# solenoid.net
KiCad netlist of a schematic drawn in EAGLE
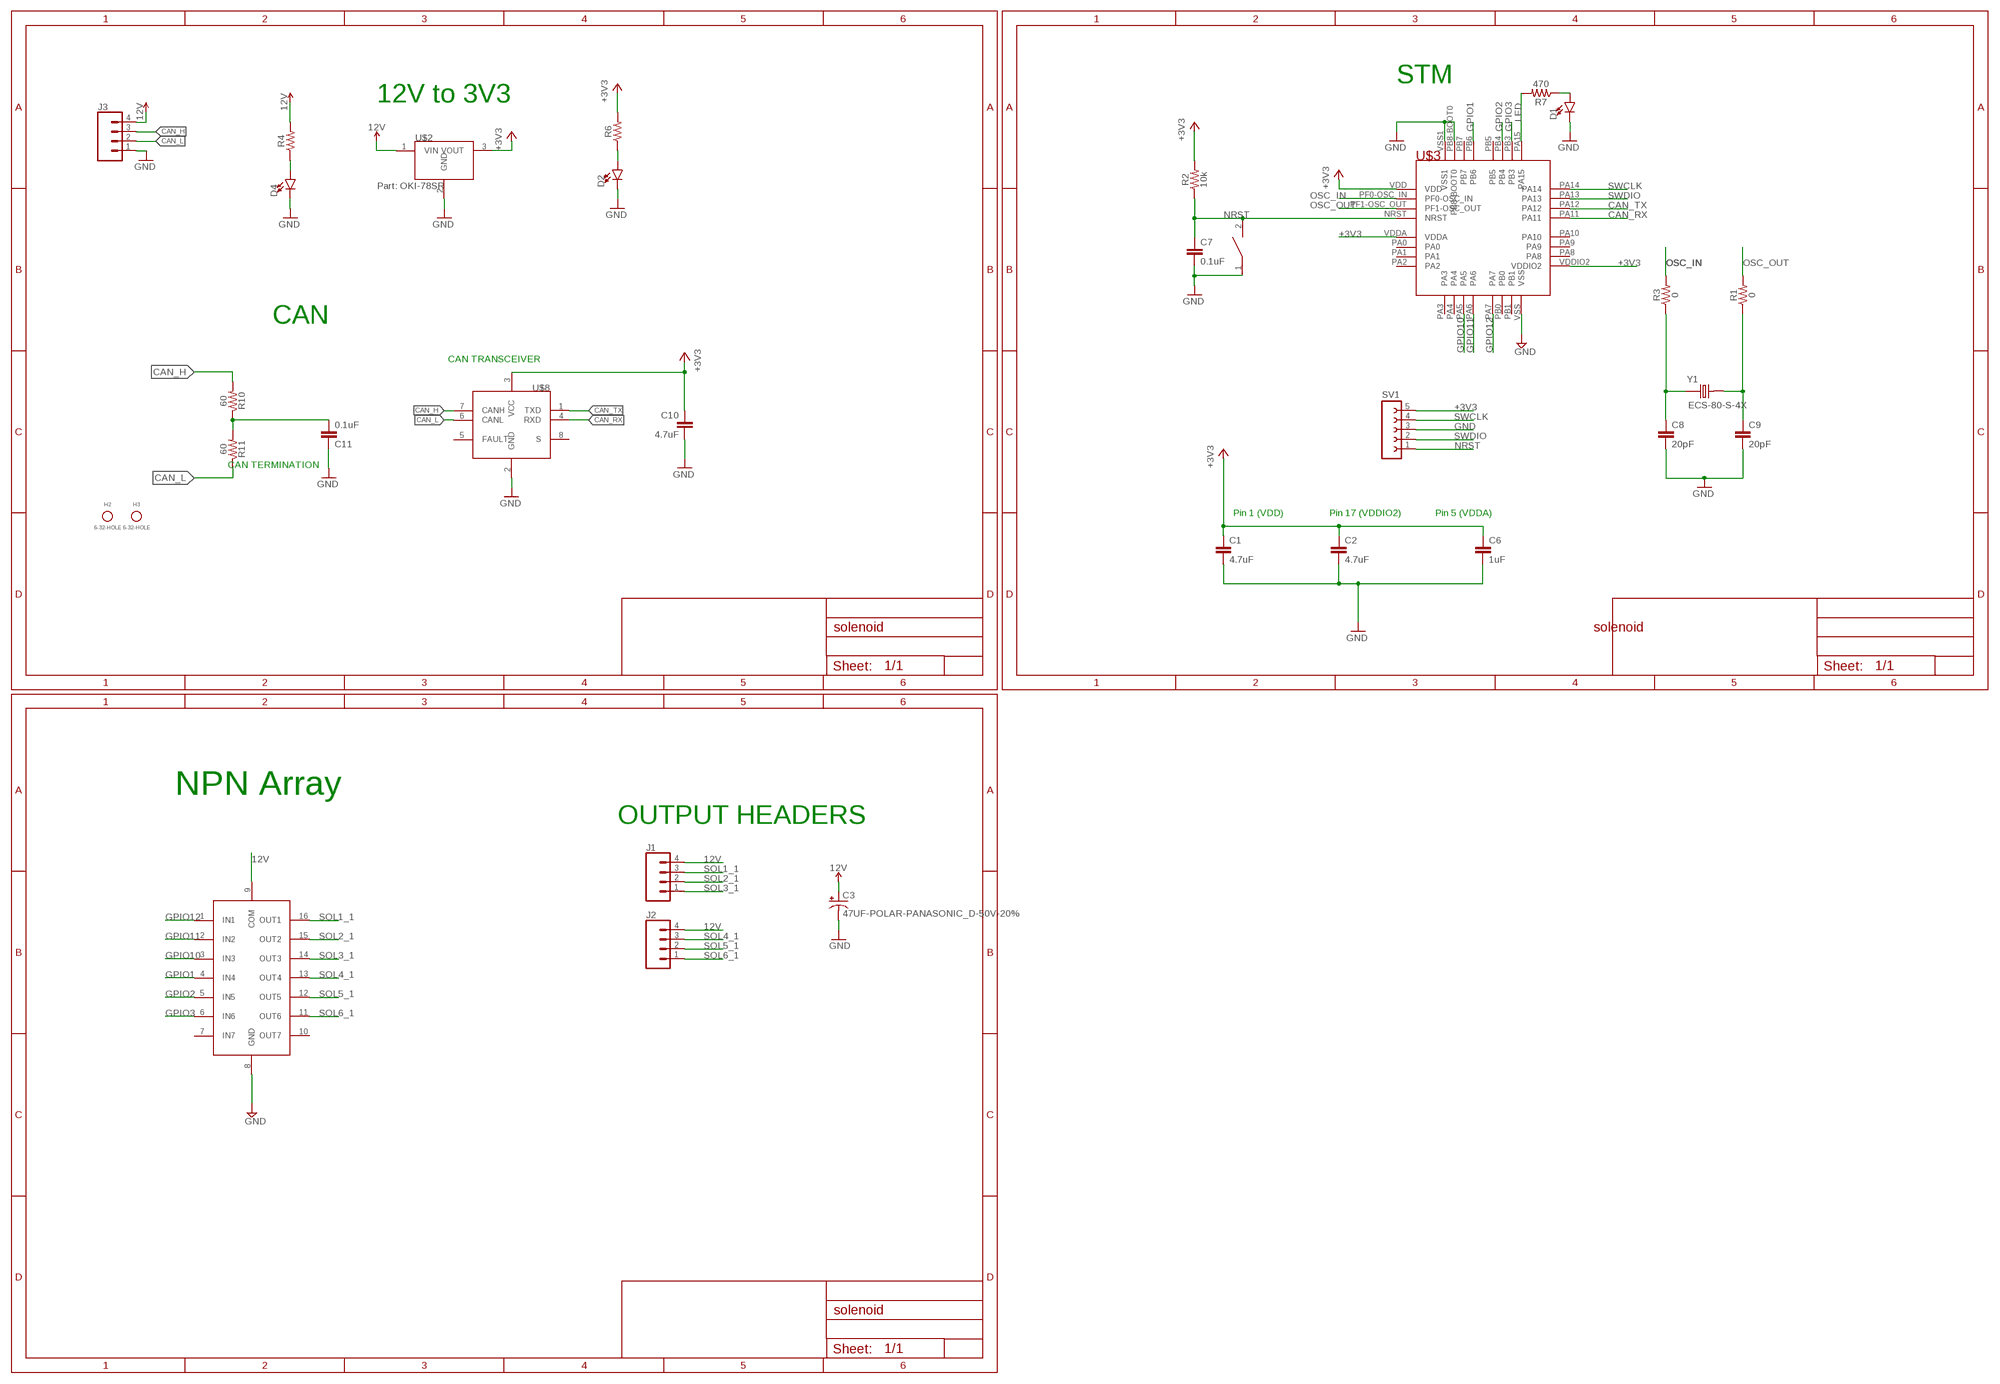
[diagram p0: schematic, sheet 1]

(export (version "E")
  (design (tool "Eeschema 10.0.6"))
  (components
    (comp (ref "C1")
      (value "4.7uF")
      (footprint "eagle-import:0603")
      (libsource (lib "eagle-import") (part "4.7UF0603"))
    )
    (comp (ref "C2")
      (value "4.7uF")
      (footprint "eagle-import:0603")
      (libsource (lib "eagle-import") (part "4.7UF0603"))
    )
    (comp (ref "C3")
      (value "47UF-POLAR-PANASONIC_D-50V-20%")
      (footprint "eagle-import:PANASONIC_D")
      (libsource (lib "eagle-import") (part "47UF-POLAR-PANASONIC_D-50V-20%"))
    )
    (comp (ref "C6")
      (value "1uF")
      (footprint "eagle-import:0603")
      (libsource (lib "eagle-import") (part "4.7UF0603"))
    )
    (comp (ref "C7")
      (value "0.1uF")
      (footprint "eagle-import:0603")
      (libsource (lib "eagle-import") (part "4.7UF0603"))
    )
    (comp (ref "C8")
      (value "20pF")
      (footprint "eagle-import:0603")
      (libsource (lib "eagle-import") (part "4.7UF0603"))
    )
    (comp (ref "C9")
      (value "20pF")
      (footprint "eagle-import:0603")
      (libsource (lib "eagle-import") (part "4.7UF0603"))
    )
    (comp (ref "C10")
      (value "4.7uF")
      (footprint "eagle-import:0603")
      (libsource (lib "eagle-import") (part "4.7UF0603"))
    )
    (comp (ref "C11")
      (value "0.1uF")
      (footprint "eagle-import:0603")
      (libsource (lib "eagle-import") (part "0.1UF-0603-25V-(+80/-20%)"))
    )
    (comp (ref "D1")
      (value "LED0603")
      (footprint "eagle-import:LED-0603")
      (libsource (lib "eagle-import") (part "LED0603"))
    )
    (comp (ref "D2")
      (value "LED0603")
      (footprint "eagle-import:LED-0603")
      (libsource (lib "eagle-import") (part "LED0603"))
    )
    (comp (ref "D4")
      (value "LED0603")
      (footprint "eagle-import:LED-0603")
      (libsource (lib "eagle-import") (part "LED0603"))
    )
    (comp (ref "H2")
      (value "6-32-HOLE")
      (footprint "eagle-import:6-32-HOLE")
      (libsource (lib "eagle-import") (part "6-32-HOLE"))
    )
    (comp (ref "H3")
      (value "6-32-HOLE")
      (footprint "eagle-import:6-32-HOLE")
      (libsource (lib "eagle-import") (part "6-32-HOLE"))
    )
    (comp (ref "J1")
      (value "PXC-PTSM-04-V-1778573")
      (footprint "eagle-import:PXC-PTSM-04-V-1778573")
      (libsource (lib "eagle-import") (part "PXC-PTSM-04-V-1778573"))
    )
    (comp (ref "J2")
      (value "PXC-PTSM-04-V-1778573")
      (footprint "eagle-import:PXC-PTSM-04-V-1778573")
      (libsource (lib "eagle-import") (part "PXC-PTSM-04-V-1778573"))
    )
    (comp (ref "J3")
      (value "PXC-PTSM-04-V-1778573")
      (footprint "eagle-import:PXC-PTSM-04-V-1778573")
      (libsource (lib "eagle-import") (part "PXC-PTSM-04-V-1778573"))
    )
    (comp (ref "R1")
      (value "0")
      (footprint "eagle-import:0603")
      (libsource (lib "eagle-import") (part "1KOHM-0603-1/10W-1%"))
    )
    (comp (ref "R2")
      (value "10k")
      (footprint "eagle-import:0603")
      (libsource (lib "eagle-import") (part "1KOHM-0603-1/10W-1%"))
    )
    (comp (ref "R3")
      (value "0")
      (footprint "eagle-import:0603")
      (libsource (lib "eagle-import") (part "1KOHM-0603-1/10W-1%"))
    )
    (comp (ref "R4")
      (value "RESISTOR0603")
      (footprint "eagle-import:0603")
      (libsource (lib "eagle-import") (part "RESISTOR0603"))
    )
    (comp (ref "R6")
      (value "RESISTOR0603")
      (footprint "eagle-import:0603")
      (libsource (lib "eagle-import") (part "RESISTOR0603"))
    )
    (comp (ref "R7")
      (value "470")
      (footprint "eagle-import:0603")
      (libsource (lib "eagle-import") (part "RESISTOR0603"))
    )
    (comp (ref "R10")
      (value "60")
      (footprint "eagle-import:0603")
      (libsource (lib "eagle-import") (part "1KOHM-0603-1/10W-1%"))
    )
    (comp (ref "R11")
      (value "60")
      (footprint "eagle-import:0603")
      (libsource (lib "eagle-import") (part "1KOHM-0603-1/10W-1%"))
    )
    (comp (ref "SV1")
      (value "FE05-1")
      (footprint "eagle-import:FE05-1")
      (libsource (lib "eagle-import") (part "FE05-1"))
    )
    (comp (ref "U$1")
      (value "DISCRETECOMPONENTS_SWITCH")
      (footprint "eagle-import:DISCRETECOMPONENTS_SW_2512")
      (libsource (lib "eagle-import") (part "DISCRETECOMPONENTS_SWITCH"))
    )
    (comp (ref "U$2")
      (value "MURATA-DC-DC")
      (footprint "eagle-import:MURATA-DC-DC")
      (libsource (lib "eagle-import") (part "MURATA-DC-DC"))
    )
    (comp (ref "U$3")
      (value "STM32F042K6T6")
      (footprint "eagle-import:STM32F042K6T6")
      (libsource (lib "eagle-import") (part "STM32F042K6T6"))
    )
    (comp (ref "U$8")
      (value "TCAN337D")
      (footprint "eagle-import:SOIC-8")
      (libsource (lib "eagle-import") (part "TCAN337D"))
    )
    (comp (ref "U1")
      (value "ULN2003V12")
      (footprint "eagle-import:ULN2003V12")
      (fields (field (name "MANUFACTURER") "Diodes Inc."))
      (libsource (lib "eagle-import") (part "ULN2003V12"))
    )
    (comp (ref "Y1")
      (value "ECS-80-S-4X")
      (footprint "eagle-import:XTAL_ECS-80-S-4X")
      (fields (field (name "DIGI-KEY_PART_NUMBER") "X1057-ND") (field (name "MF") "ECS International"))
      (libsource (lib "eagle-import") (part "ECS-80-S-4X"))
    )
  )
  (nets
    (net (code "1") (name "+3V3") (class "Default")
      (node (ref "C1") (pin "1") (pinfunction "1_1") (pintype "passive"))
      (node (ref "C10") (pin "1") (pinfunction "1_1") (pintype "passive"))
      (node (ref "C2") (pin "1") (pinfunction "1_1") (pintype "passive"))
      (node (ref "C6") (pin "1") (pinfunction "1_1") (pintype "passive"))
      (node (ref "R2") (pin "2") (pinfunction "2_2") (pintype "passive"))
      (node (ref "R6") (pin "2") (pinfunction "2_2") (pintype "passive"))
      (node (ref "SV1") (pin "5") (pinfunction "5_5") (pintype "passive"))
      (node (ref "U$2") (pin "3") (pinfunction "VOUT_3") (pintype "bidirectional"))
      (node (ref "U$3") (pin "VDD") (pinfunction "VDD_VDD") (pintype "bidirectional"))
      (node (ref "U$3") (pin "VDDA") (pinfunction "VDDA_VDDA") (pintype "bidirectional"))
      (node (ref "U$3") (pin "VDDIO2") (pinfunction "VDDIO2_VDDIO2") (pintype "bidirectional"))
      (node (ref "U$8") (pin "3") (pinfunction "VCC_3") (pintype "bidirectional"))
    )
    (net (code "2") (name "/GPIO1") (class "Default")
      (node (ref "U$3") (pin "PB6") (pinfunction "PB6_PB6") (pintype "bidirectional"))
      (node (ref "U1") (pin "4") (pinfunction "IN4_4") (pintype "bidirectional"))
    )
    (net (code "3") (name "/GPIO2") (class "Default")
      (node (ref "U$3") (pin "PB4") (pinfunction "PB4_PB4") (pintype "bidirectional"))
      (node (ref "U1") (pin "5") (pinfunction "IN5_5") (pintype "bidirectional"))
    )
    (net (code "4") (name "/GPIO3") (class "Default")
      (node (ref "U$3") (pin "PB3") (pinfunction "PB3_PB3") (pintype "bidirectional"))
      (node (ref "U1") (pin "6") (pinfunction "IN6_6") (pintype "bidirectional"))
    )
    (net (code "5") (name "/GPIO10") (class "Default")
      (node (ref "U$3") (pin "PA5") (pinfunction "PA5_PA5") (pintype "bidirectional"))
      (node (ref "U1") (pin "3") (pinfunction "IN3_3") (pintype "bidirectional"))
    )
    (net (code "6") (name "/GPIO11") (class "Default")
      (node (ref "U$3") (pin "PA6") (pinfunction "PA6_PA6") (pintype "bidirectional"))
      (node (ref "U1") (pin "2") (pinfunction "IN2_2") (pintype "bidirectional"))
    )
    (net (code "7") (name "/GPIO12") (class "Default")
      (node (ref "U$3") (pin "PA7") (pinfunction "PA7_PA7") (pintype "bidirectional"))
      (node (ref "U1") (pin "1") (pinfunction "IN1_1") (pintype "bidirectional"))
    )
    (net (code "8") (name "/LED") (class "Default")
      (node (ref "R7") (pin "2") (pinfunction "2_2") (pintype "passive"))
      (node (ref "U$3") (pin "PA15") (pinfunction "PA15_PA15") (pintype "bidirectional"))
    )
    (net (code "9") (name "/NRST") (class "Default")
      (node (ref "C7") (pin "1") (pinfunction "1_1") (pintype "passive"))
      (node (ref "R2") (pin "1") (pinfunction "1_1") (pintype "passive"))
      (node (ref "SV1") (pin "1") (pinfunction "1_1") (pintype "passive"))
      (node (ref "U$1") (pin "2") (pinfunction "P$2_2") (pintype "bidirectional"))
      (node (ref "U$3") (pin "NRST") (pinfunction "NRST_NRST") (pintype "bidirectional"))
    )
    (net (code "10") (name "/OSC_IN") (class "Default")
      (node (ref "R3") (pin "2") (pinfunction "2_2") (pintype "passive"))
      (node (ref "U$3") (pin "PF0-OSC_IN") (pinfunction "PF0-OSC_IN_PF0-OSC_IN") (pintype "bidirectional"))
    )
    (net (code "11") (name "/OSC_OUT") (class "Default")
      (node (ref "R1") (pin "2") (pinfunction "2_2") (pintype "passive"))
      (node (ref "U$3") (pin "PF1-OSC_OUT") (pinfunction "PF1-OSC_OUT_PF1-OSC_OUT") (pintype "bidirectional"))
    )
    (net (code "12") (name "/SOL1_1") (class "Default")
      (node (ref "J1") (pin "3") (pinfunction "3_3") (pintype "passive"))
      (node (ref "U1") (pin "16") (pinfunction "OUT1_16") (pintype "bidirectional"))
    )
    (net (code "13") (name "/SOL2_1") (class "Default")
      (node (ref "J1") (pin "2") (pinfunction "2_2") (pintype "passive"))
      (node (ref "U1") (pin "15") (pinfunction "OUT2_15") (pintype "bidirectional"))
    )
    (net (code "14") (name "/SOL3_1") (class "Default")
      (node (ref "J1") (pin "1") (pinfunction "1_1") (pintype "passive"))
      (node (ref "U1") (pin "14") (pinfunction "OUT3_14") (pintype "bidirectional"))
    )
    (net (code "15") (name "/SOL4_1") (class "Default")
      (node (ref "J2") (pin "3") (pinfunction "3_3") (pintype "passive"))
      (node (ref "U1") (pin "13") (pinfunction "OUT4_13") (pintype "bidirectional"))
    )
    (net (code "16") (name "/SOL5_1") (class "Default")
      (node (ref "J2") (pin "2") (pinfunction "2_2") (pintype "passive"))
      (node (ref "U1") (pin "12") (pinfunction "OUT5_12") (pintype "bidirectional"))
    )
    (net (code "17") (name "/SOL6_1") (class "Default")
      (node (ref "J2") (pin "1") (pinfunction "1_1") (pintype "passive"))
      (node (ref "U1") (pin "11") (pinfunction "OUT6_11") (pintype "bidirectional"))
    )
    (net (code "18") (name "/SWCLK") (class "Default")
      (node (ref "SV1") (pin "4") (pinfunction "4_4") (pintype "passive"))
      (node (ref "U$3") (pin "PA14") (pinfunction "PA14_PA14") (pintype "bidirectional"))
    )
    (net (code "19") (name "/SWDIO") (class "Default")
      (node (ref "SV1") (pin "2") (pinfunction "2_2") (pintype "passive"))
      (node (ref "U$3") (pin "PA13") (pinfunction "PA13_PA13") (pintype "bidirectional"))
    )
    (net (code "20") (name "12V") (class "Default")
      (node (ref "C3") (pin "+") (pinfunction "+_+") (pintype "passive"))
      (node (ref "J1") (pin "4") (pinfunction "4_4") (pintype "passive"))
      (node (ref "J2") (pin "4") (pinfunction "4_4") (pintype "passive"))
      (node (ref "J3") (pin "4") (pinfunction "4_4") (pintype "passive"))
      (node (ref "R4") (pin "2") (pinfunction "2_2") (pintype "passive"))
      (node (ref "U$2") (pin "1") (pinfunction "VIN_1") (pintype "bidirectional"))
      (node (ref "U1") (pin "9") (pinfunction "COM_9") (pintype "bidirectional"))
    )
    (net (code "21") (name "CAN_H") (class "Default")
      (node (ref "J3") (pin "3") (pinfunction "3_3") (pintype "passive"))
      (node (ref "R10") (pin "2") (pinfunction "2_2") (pintype "passive"))
      (node (ref "U$8") (pin "7") (pinfunction "CANH_7") (pintype "bidirectional"))
    )
    (net (code "22") (name "CAN_L") (class "Default")
      (node (ref "J3") (pin "2") (pinfunction "2_2") (pintype "passive"))
      (node (ref "R11") (pin "1") (pinfunction "1_1") (pintype "passive"))
      (node (ref "U$8") (pin "6") (pinfunction "CANL_6") (pintype "bidirectional"))
    )
    (net (code "23") (name "CAN_RX") (class "Default")
      (node (ref "U$3") (pin "PA11") (pinfunction "PA11_PA11") (pintype "bidirectional"))
      (node (ref "U$8") (pin "4") (pinfunction "RXD_4") (pintype "bidirectional"))
    )
    (net (code "24") (name "CAN_TX") (class "Default")
      (node (ref "U$3") (pin "PA12") (pinfunction "PA12_PA12") (pintype "bidirectional"))
      (node (ref "U$8") (pin "1") (pinfunction "TXD_1") (pintype "bidirectional"))
    )
    (net (code "25") (name "GND") (class "Default")
      (node (ref "C1") (pin "2") (pinfunction "2_2") (pintype "passive"))
      (node (ref "C10") (pin "2") (pinfunction "2_2") (pintype "passive"))
      (node (ref "C11") (pin "1") (pinfunction "1_1") (pintype "passive"))
      (node (ref "C2") (pin "2") (pinfunction "2_2") (pintype "passive"))
      (node (ref "C3") (pin "-") (pinfunction "-_-") (pintype "passive"))
      (node (ref "C6") (pin "2") (pinfunction "2_2") (pintype "passive"))
      (node (ref "C7") (pin "2") (pinfunction "2_2") (pintype "passive"))
      (node (ref "C8") (pin "2") (pinfunction "2_2") (pintype "passive"))
      (node (ref "C9") (pin "2") (pinfunction "2_2") (pintype "passive"))
      (node (ref "D1") (pin "C") (pinfunction "C_C") (pintype "passive"))
      (node (ref "D2") (pin "C") (pinfunction "C_C") (pintype "passive"))
      (node (ref "D4") (pin "C") (pinfunction "C_C") (pintype "passive"))
      (node (ref "J3") (pin "1") (pinfunction "1_1") (pintype "passive"))
      (node (ref "SV1") (pin "3") (pinfunction "3_3") (pintype "passive"))
      (node (ref "U$1") (pin "1") (pinfunction "P$1_1") (pintype "bidirectional"))
      (node (ref "U$2") (pin "2") (pinfunction "GND_2") (pintype "bidirectional"))
      (node (ref "U$3") (pin "PB8-BOOT0") (pinfunction "PB8-BOOT0_PB8-BOOT0") (pintype "bidirectional"))
      (node (ref "U$3") (pin "VSS") (pinfunction "VSS_VSS") (pintype "bidirectional"))
      (node (ref "U$3") (pin "VSS1") (pinfunction "VSS1_VSS1") (pintype "bidirectional"))
      (node (ref "U$8") (pin "2") (pinfunction "GND_2") (pintype "bidirectional"))
      (node (ref "U1") (pin "8") (pinfunction "GND_8") (pintype "bidirectional"))
    )
    (net (code "26") (name "Net-(C8-Pad1)") (class "Default")
      (node (ref "C8") (pin "1") (pinfunction "1_1") (pintype "passive"))
      (node (ref "R3") (pin "1") (pinfunction "1_1") (pintype "passive"))
      (node (ref "Y1") (pin "1") (pinfunction "1_1") (pintype "passive"))
    )
    (net (code "27") (name "Net-(C9-Pad1)") (class "Default")
      (node (ref "C9") (pin "1") (pinfunction "1_1") (pintype "passive"))
      (node (ref "R1") (pin "1") (pinfunction "1_1") (pintype "passive"))
      (node (ref "Y1") (pin "2") (pinfunction "2_2") (pintype "passive"))
    )
    (net (code "28") (name "Net-(C11-Pad2)") (class "Default")
      (node (ref "C11") (pin "2") (pinfunction "2_2") (pintype "passive"))
      (node (ref "R10") (pin "1") (pinfunction "1_1") (pintype "passive"))
      (node (ref "R11") (pin "2") (pinfunction "2_2") (pintype "passive"))
    )
    (net (code "29") (name "Net-(D1-PadA)") (class "Default")
      (node (ref "D1") (pin "A") (pinfunction "A_A") (pintype "passive"))
      (node (ref "R7") (pin "1") (pinfunction "1_1") (pintype "passive"))
    )
    (net (code "30") (name "Net-(D2-PadA)") (class "Default")
      (node (ref "D2") (pin "A") (pinfunction "A_A") (pintype "passive"))
      (node (ref "R6") (pin "1") (pinfunction "1_1") (pintype "passive"))
    )
    (net (code "31") (name "Net-(D4-PadA)") (class "Default")
      (node (ref "D4") (pin "A") (pinfunction "A_A") (pintype "passive"))
      (node (ref "R4") (pin "1") (pinfunction "1_1") (pintype "passive"))
    )
    (net (code "32") (name "unconnected-(U$3-PadPA0)") (class "Default")
      (node (ref "U$3") (pin "PA0") (pinfunction "PA0_PA0") (pintype "bidirectional"))
    )
    (net (code "33") (name "unconnected-(U$3-PadPA1)") (class "Default")
      (node (ref "U$3") (pin "PA1") (pinfunction "PA1_PA1") (pintype "bidirectional"))
    )
    (net (code "34") (name "unconnected-(U$3-PadPA2)") (class "Default")
      (node (ref "U$3") (pin "PA2") (pinfunction "PA2_PA2") (pintype "bidirectional"))
    )
    (net (code "35") (name "unconnected-(U$3-PadPA3)") (class "Default")
      (node (ref "U$3") (pin "PA3") (pinfunction "PA3_PA3") (pintype "bidirectional"))
    )
    (net (code "36") (name "unconnected-(U$3-PadPA4)") (class "Default")
      (node (ref "U$3") (pin "PA4") (pinfunction "PA4_PA4") (pintype "bidirectional"))
    )
    (net (code "37") (name "unconnected-(U$3-PadPA8)") (class "Default")
      (node (ref "U$3") (pin "PA8") (pinfunction "PA8_PA8") (pintype "bidirectional"))
    )
    (net (code "38") (name "unconnected-(U$3-PadPA9)") (class "Default")
      (node (ref "U$3") (pin "PA9") (pinfunction "PA9_PA9") (pintype "bidirectional"))
    )
    (net (code "39") (name "unconnected-(U$3-PadPA10)") (class "Default")
      (node (ref "U$3") (pin "PA10") (pinfunction "PA10_PA10") (pintype "bidirectional"))
    )
    (net (code "40") (name "unconnected-(U$3-PadPB0)") (class "Default")
      (node (ref "U$3") (pin "PB0") (pinfunction "PB0_PB0") (pintype "bidirectional"))
    )
    (net (code "41") (name "unconnected-(U$3-PadPB1)") (class "Default")
      (node (ref "U$3") (pin "PB1") (pinfunction "PB1_PB1") (pintype "bidirectional"))
    )
    (net (code "42") (name "unconnected-(U$3-PadPB5)") (class "Default")
      (node (ref "U$3") (pin "PB5") (pinfunction "PB5_PB5") (pintype "bidirectional"))
    )
    (net (code "43") (name "unconnected-(U$3-PadPB7)") (class "Default")
      (node (ref "U$3") (pin "PB7") (pinfunction "PB7_PB7") (pintype "bidirectional"))
    )
    (net (code "44") (name "unconnected-(U$8-FAULT-Pad5)") (class "Default")
      (node (ref "U$8") (pin "5") (pinfunction "FAULT_5") (pintype "bidirectional"))
    )
    (net (code "45") (name "unconnected-(U$8-S-Pad8)") (class "Default")
      (node (ref "U$8") (pin "8") (pinfunction "S_8") (pintype "bidirectional"))
    )
    (net (code "46") (name "unconnected-(U1-IN7-Pad7)") (class "Default")
      (node (ref "U1") (pin "7") (pinfunction "IN7_7") (pintype "bidirectional"))
    )
    (net (code "47") (name "unconnected-(U1-OUT7-Pad10)") (class "Default")
      (node (ref "U1") (pin "10") (pinfunction "OUT7_10") (pintype "bidirectional"))
    )
  )
)
